# sensor_board.net
KiCad netlist of a schematic drawn in EAGLE
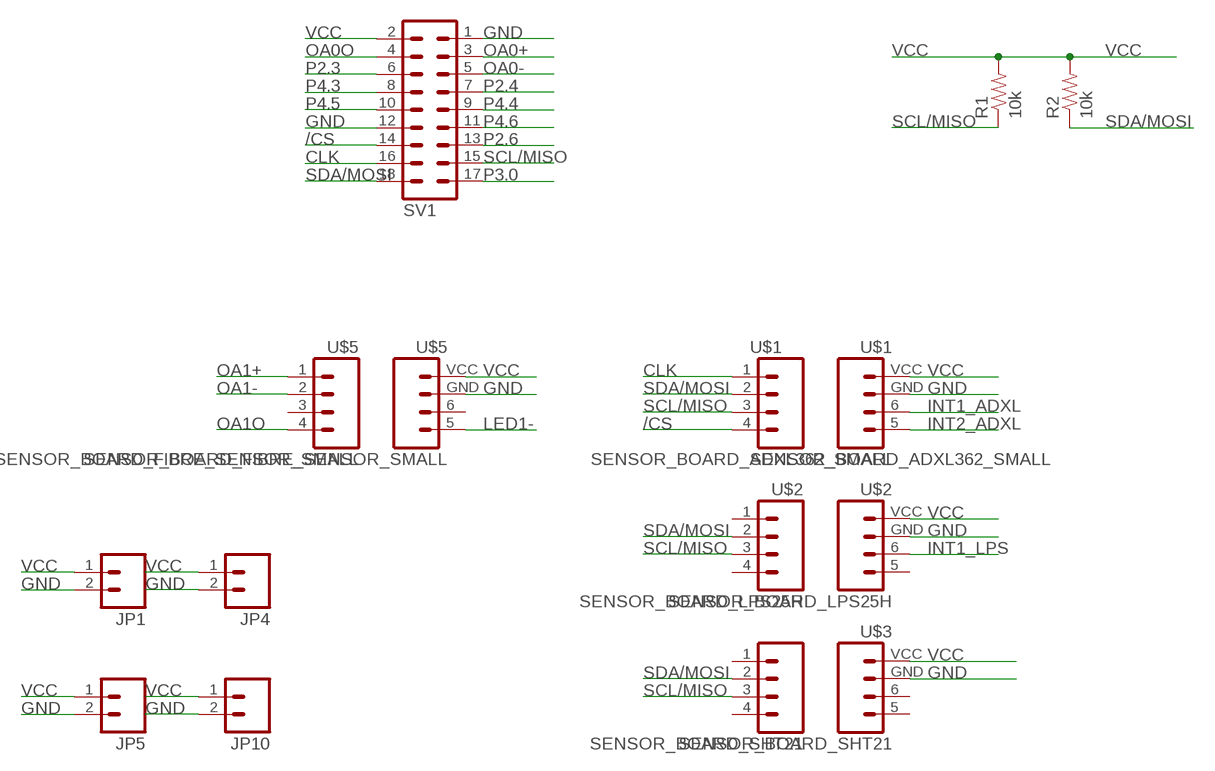
[diagram p0: schematic, sheet 1]

(export (version "E")
  (design (tool "Eeschema 10.0.6"))
  (components
    (comp (ref "JP1")
      (value "M02PTH")
      (footprint "eagle-import:1X02")
      (libsource (lib "eagle-import") (part "M02PTH"))
    )
    (comp (ref "JP4")
      (value "M02PTH")
      (footprint "eagle-import:1X02")
      (libsource (lib "eagle-import") (part "M02PTH"))
    )
    (comp (ref "JP5")
      (value "M02PTH")
      (footprint "eagle-import:1X02")
      (libsource (lib "eagle-import") (part "M02PTH"))
    )
    (comp (ref "JP10")
      (value "M02PTH")
      (footprint "eagle-import:1X02")
      (libsource (lib "eagle-import") (part "M02PTH"))
    )
    (comp (ref "R1")
      (value "10k")
      (footprint "eagle-import:AXIAL-0.3")
      (libsource (lib "eagle-import") (part "10KOHM-1/4W-1%(PTH)HORIZ"))
    )
    (comp (ref "R2")
      (value "10k")
      (footprint "eagle-import:AXIAL-0.3")
      (libsource (lib "eagle-import") (part "10KOHM-1/4W-1%(PTH)HORIZ"))
    )
    (comp (ref "SV1")
      (value "MA09-2")
      (footprint "eagle-import:MA09-2")
      (libsource (lib "eagle-import") (part "MA09-2"))
    )
    (comp (ref "U$1")
      (value "SENSOR_BOARD_ADXL362_SMALL")
      (footprint "eagle-import:SENSOR_BOARD_GEN_SMALL")
      (libsource (lib "eagle-import") (part "SENSOR_BOARD_ADXL362_SMALL"))
    )
    (comp (ref "U$2")
      (value "SENSOR_BOARD_LPS25H")
      (footprint "eagle-import:SENSOR_BOARD_GEN")
      (libsource (lib "eagle-import") (part "SENSOR_BOARD_LPS25H"))
    )
    (comp (ref "U$3")
      (value "SENSOR_BOARD_SHT21")
      (footprint "eagle-import:SENSOR_BOARD_GEN")
      (libsource (lib "eagle-import") (part "SENSOR_BOARD_SHT21"))
    )
    (comp (ref "U$5")
      (value "SENSOR_BOARD_FIBRE_SENSOR_SMALL")
      (footprint "eagle-import:SENSOR_BOARD_GEN_SMALL")
      (libsource (lib "eagle-import") (part "SENSOR_BOARD_FIBRE_SENSOR_SMALL"))
    )
  )
  (nets
    (net (code "1") (name "/CLK") (class "Default")
      (node (ref "SV1") (pin "16") (pinfunction "16_16") (pintype "passive"))
      (node (ref "U$1") (pin "1") (pinfunction "CLK_1") (pintype "passive"))
    )
    (net (code "2") (name "/GND") (class "Default")
      (node (ref "JP1") (pin "2") (pinfunction "2_2") (pintype "passive"))
      (node (ref "JP10") (pin "2") (pinfunction "2_2") (pintype "passive"))
      (node (ref "JP4") (pin "2") (pinfunction "2_2") (pintype "passive"))
      (node (ref "JP5") (pin "2") (pinfunction "2_2") (pintype "passive"))
      (node (ref "SV1") (pin "1") (pinfunction "1_1") (pintype "passive"))
      (node (ref "SV1") (pin "12") (pinfunction "12_12") (pintype "passive"))
      (node (ref "U$1") (pin "GND") (pinfunction "GND_GND") (pintype "passive"))
      (node (ref "U$2") (pin "GND") (pinfunction "GND_GND") (pintype "passive"))
      (node (ref "U$3") (pin "GND") (pinfunction "GND_GND") (pintype "passive"))
      (node (ref "U$5") (pin "GND") (pinfunction "GND_GND") (pintype "passive"))
    )
    (net (code "3") (name "/INT1_ADXL") (class "Default")
      (node (ref "U$1") (pin "6") (pinfunction "INT1_6") (pintype "passive"))
    )
    (net (code "4") (name "/INT1_LPS") (class "Default")
      (node (ref "U$2") (pin "6") (pinfunction "INT1_6") (pintype "passive"))
    )
    (net (code "5") (name "/INT2_ADXL") (class "Default")
      (node (ref "U$1") (pin "5") (pinfunction "INT2_5") (pintype "passive"))
    )
    (net (code "6") (name "/LED1-") (class "Default")
      (node (ref "U$5") (pin "5") (pinfunction "LED-_5") (pintype "passive"))
    )
    (net (code "7") (name "/OA0+") (class "Default")
      (node (ref "SV1") (pin "3") (pinfunction "3_3") (pintype "passive"))
    )
    (net (code "8") (name "/OA0-") (class "Default")
      (node (ref "SV1") (pin "5") (pinfunction "5_5") (pintype "passive"))
    )
    (net (code "9") (name "/OA0O") (class "Default")
      (node (ref "SV1") (pin "4") (pinfunction "4_4") (pintype "passive"))
    )
    (net (code "10") (name "/OA1+") (class "Default")
      (node (ref "U$5") (pin "1") (pinfunction "OA+_1") (pintype "passive"))
    )
    (net (code "11") (name "/OA1-") (class "Default")
      (node (ref "U$5") (pin "2") (pinfunction "OA-_2") (pintype "passive"))
    )
    (net (code "12") (name "/OA1O") (class "Default")
      (node (ref "U$5") (pin "4") (pinfunction "OAO_4") (pintype "passive"))
    )
    (net (code "13") (name "/P2.3") (class "Default")
      (node (ref "SV1") (pin "6") (pinfunction "6_6") (pintype "passive"))
    )
    (net (code "14") (name "/P2.4") (class "Default")
      (node (ref "SV1") (pin "7") (pinfunction "7_7") (pintype "passive"))
    )
    (net (code "15") (name "/P2.6") (class "Default")
      (node (ref "SV1") (pin "13") (pinfunction "13_13") (pintype "passive"))
    )
    (net (code "16") (name "/P3.0") (class "Default")
      (node (ref "SV1") (pin "17") (pinfunction "17_17") (pintype "passive"))
    )
    (net (code "17") (name "/P4.3") (class "Default")
      (node (ref "SV1") (pin "8") (pinfunction "8_8") (pintype "passive"))
    )
    (net (code "18") (name "/P4.4") (class "Default")
      (node (ref "SV1") (pin "9") (pinfunction "9_9") (pintype "passive"))
    )
    (net (code "19") (name "/P4.5") (class "Default")
      (node (ref "SV1") (pin "10") (pinfunction "10_10") (pintype "passive"))
    )
    (net (code "20") (name "/P4.6") (class "Default")
      (node (ref "SV1") (pin "11") (pinfunction "11_11") (pintype "passive"))
    )
    (net (code "21") (name "/SCL{slash}MISO") (class "Default")
      (node (ref "R1") (pin "P$1") (pinfunction "1_P$1") (pintype "passive"))
      (node (ref "SV1") (pin "15") (pinfunction "15_15") (pintype "passive"))
      (node (ref "U$1") (pin "3") (pinfunction "MISO_3") (pintype "passive"))
      (node (ref "U$2") (pin "3") (pinfunction "SCL_3") (pintype "passive"))
      (node (ref "U$3") (pin "3") (pinfunction "SCL_3") (pintype "passive"))
    )
    (net (code "22") (name "/SDA{slash}MOSI") (class "Default")
      (node (ref "R2") (pin "P$1") (pinfunction "1_P$1") (pintype "passive"))
      (node (ref "SV1") (pin "18") (pinfunction "18_18") (pintype "passive"))
      (node (ref "U$1") (pin "2") (pinfunction "MOSI_2") (pintype "passive"))
      (node (ref "U$2") (pin "2") (pinfunction "SDA_2") (pintype "passive"))
      (node (ref "U$3") (pin "2") (pinfunction "SDA_2") (pintype "passive"))
    )
    (net (code "23") (name "/VCC") (class "Default")
      (node (ref "JP1") (pin "1") (pinfunction "1_1") (pintype "passive"))
      (node (ref "JP10") (pin "1") (pinfunction "1_1") (pintype "passive"))
      (node (ref "JP4") (pin "1") (pinfunction "1_1") (pintype "passive"))
      (node (ref "JP5") (pin "1") (pinfunction "1_1") (pintype "passive"))
      (node (ref "R1") (pin "P$2") (pinfunction "2_P$2") (pintype "passive"))
      (node (ref "R2") (pin "P$2") (pinfunction "2_P$2") (pintype "passive"))
      (node (ref "SV1") (pin "2") (pinfunction "2_2") (pintype "passive"))
      (node (ref "U$1") (pin "VCC") (pinfunction "VCC_VCC") (pintype "passive"))
      (node (ref "U$2") (pin "VCC") (pinfunction "VCC_VCC") (pintype "passive"))
      (node (ref "U$3") (pin "VCC") (pinfunction "VCC_VCC") (pintype "passive"))
      (node (ref "U$5") (pin "VCC") (pinfunction "VCC_VCC") (pintype "passive"))
    )
    (net (code "24") (name "/{slash}CS") (class "Default")
      (node (ref "SV1") (pin "14") (pinfunction "14_14") (pintype "passive"))
      (node (ref "U$1") (pin "4") (pinfunction "/CS_4") (pintype "passive"))
    )
    (net (code "25") (name "unconnected-(U$2-Pad1)") (class "Default")
      (node (ref "U$2") (pin "1") (pinfunction "1_1") (pintype "passive"))
    )
    (net (code "26") (name "unconnected-(U$2-Pad4)") (class "Default")
      (node (ref "U$2") (pin "4") (pinfunction "4_4") (pintype "passive"))
    )
    (net (code "27") (name "unconnected-(U$2-Pad5)") (class "Default")
      (node (ref "U$2") (pin "5") (pinfunction "5_5") (pintype "passive"))
    )
    (net (code "28") (name "unconnected-(U$3-Pad1)") (class "Default")
      (node (ref "U$3") (pin "1") (pinfunction "1_1") (pintype "passive"))
    )
    (net (code "29") (name "unconnected-(U$3-Pad4)") (class "Default")
      (node (ref "U$3") (pin "4") (pinfunction "4_4") (pintype "passive"))
    )
    (net (code "30") (name "unconnected-(U$3-Pad5)") (class "Default")
      (node (ref "U$3") (pin "5") (pinfunction "5_5") (pintype "passive"))
    )
    (net (code "31") (name "unconnected-(U$3-Pad6)") (class "Default")
      (node (ref "U$3") (pin "6") (pinfunction "6_6") (pintype "passive"))
    )
    (net (code "32") (name "unconnected-(U$5-Pad3)") (class "Default")
      (node (ref "U$5") (pin "3") (pinfunction "3_3") (pintype "passive"))
    )
    (net (code "33") (name "unconnected-(U$5-Pad6)") (class "Default")
      (node (ref "U$5") (pin "6") (pinfunction "6_6") (pintype "passive"))
    )
  )
)
